# Trofodotiko.net
KiCad netlist of a schematic drawn in EAGLE
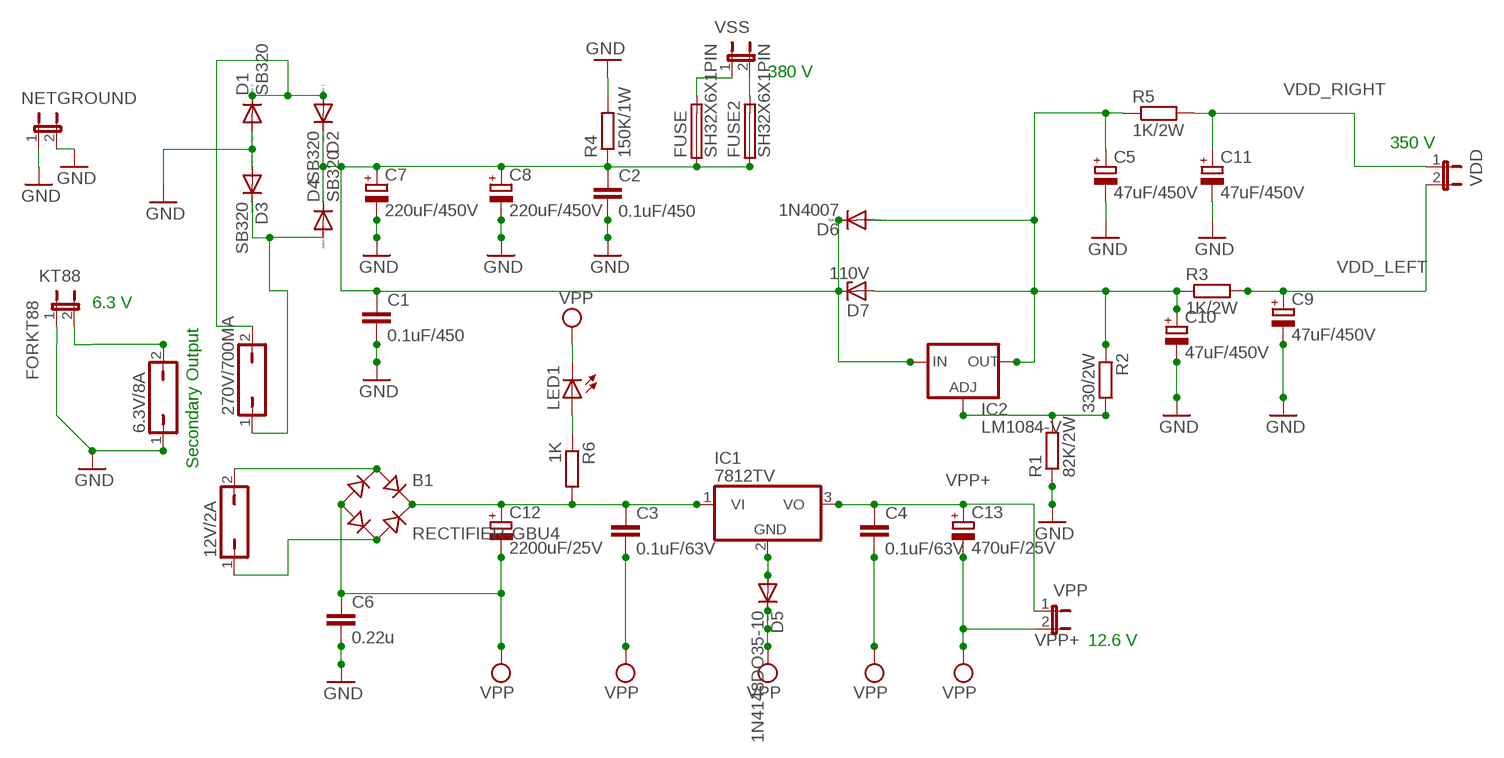
[diagram p0: schematic, sheet 1]

(export (version "E")
  (design (tool "Eeschema 10.0.6"))
  (components
    (comp (ref "6.3V/8A")
      (value "JP1Q")
      (footprint "eagle-import:JP1")
      (libsource (lib "eagle-import") (part "JP1Q"))
    )
    (comp (ref "12V/2A")
      (value "JP1Q")
      (footprint "eagle-import:JP1")
      (libsource (lib "eagle-import") (part "JP1Q"))
    )
    (comp (ref "270V/700MA")
      (value "JP1Q")
      (footprint "eagle-import:JP1")
      (libsource (lib "eagle-import") (part "JP1Q"))
    )
    (comp (ref "B1")
      (value "RECTIFIER-GBU4")
      (footprint "eagle-import:GBU4")
      (libsource (lib "eagle-import") (part "RECTIFIER-GBU4"))
    )
    (comp (ref "C1")
      (value "0.1uF/450")
      (footprint "eagle-import:C10B5")
      (libsource (lib "eagle-import") (part "C10/5"))
    )
    (comp (ref "C2")
      (value "0.1uF/450")
      (footprint "eagle-import:C10B5")
      (libsource (lib "eagle-import") (part "C10/5"))
    )
    (comp (ref "C3")
      (value "0.1uF/63V")
      (footprint "eagle-import:C5B2.5")
      (libsource (lib "eagle-import") (part "C5/2.5"))
    )
    (comp (ref "C4")
      (value "0.1uF/63V")
      (footprint "eagle-import:C5B2.5")
      (libsource (lib "eagle-import") (part "C5/2.5"))
    )
    (comp (ref "C5")
      (value "47uF/450V")
      (footprint "eagle-import:E5-13")
      (libsource (lib "eagle-import") (part "CPOL-EUE5-13"))
    )
    (comp (ref "C6")
      (value "0.22u")
      (footprint "eagle-import:C0805K")
      (libsource (lib "eagle-import") (part "C-EUC0805K"))
    )
    (comp (ref "C7")
      (value "220uF/450V")
      (footprint "eagle-import:EB25D")
      (libsource (lib "eagle-import") (part "CPOL-EUE10-25"))
    )
    (comp (ref "C8")
      (value "220uF/450V")
      (footprint "eagle-import:EB25D")
      (libsource (lib "eagle-import") (part "CPOL-EUE10-25"))
    )
    (comp (ref "C9")
      (value "47uF/450V")
      (footprint "eagle-import:E5-13")
      (libsource (lib "eagle-import") (part "CPOL-EUE5-13"))
    )
    (comp (ref "C10")
      (value "47uF/450V")
      (footprint "eagle-import:E5-13")
      (libsource (lib "eagle-import") (part "CPOL-EUE5-13"))
    )
    (comp (ref "C11")
      (value "47uF/450V")
      (footprint "eagle-import:E5-13")
      (libsource (lib "eagle-import") (part "CPOL-EUE5-13"))
    )
    (comp (ref "C12")
      (value "2200uF/25V")
      (footprint "eagle-import:E5-13")
      (libsource (lib "eagle-import") (part "CPOL-EUE5-13"))
    )
    (comp (ref "C13")
      (value "470uF/25V")
      (footprint "eagle-import:E3,5-8")
      (libsource (lib "eagle-import") (part "CPOL-EUE3.5-8"))
    )
    (comp (ref "D1")
      (value "SB320")
      (footprint "eagle-import:DO201-15")
      (libsource (lib "eagle-import") (part "SB320"))
    )
    (comp (ref "D2")
      (value "SB320")
      (footprint "eagle-import:DO201-15")
      (libsource (lib "eagle-import") (part "SB320"))
    )
    (comp (ref "D3")
      (value "SB320")
      (footprint "eagle-import:DO201-15")
      (libsource (lib "eagle-import") (part "SB320"))
    )
    (comp (ref "D4")
      (value "SB320")
      (footprint "eagle-import:DO201-15")
      (libsource (lib "eagle-import") (part "SB320"))
    )
    (comp (ref "D5")
      (value "1N4148DO35-10")
      (footprint "eagle-import:DO35-10")
      (libsource (lib "eagle-import") (part "1N4148DO35-10"))
    )
    (comp (ref "D6")
      (value "1N4007")
      (footprint "eagle-import:DO15-12")
      (libsource (lib "eagle-import") (part "1N5060GP"))
    )
    (comp (ref "D7")
      (value "110V")
      (footprint "eagle-import:C1702-15")
      (libsource (lib "eagle-import") (part "1N5333"))
    )
    (comp (ref "FUSE")
      (value "SH32X6X1PIN")
      (footprint "eagle-import:SH32")
      (libsource (lib "eagle-import") (part "SH32X6X1PIN"))
    )
    (comp (ref "FUSE2")
      (value "SH32X6X1PIN")
      (footprint "eagle-import:SH32")
      (libsource (lib "eagle-import") (part "SH32X6X1PIN"))
    )
    (comp (ref "IC1")
      (value "7812TV")
      (footprint "eagle-import:TO220V")
      (libsource (lib "eagle-import") (part "78TV12"))
    )
    (comp (ref "IC2")
      (value "LM1084-V")
      (footprint "eagle-import:317TS")
      (libsource (lib "eagle-import") (part "LM1084-V"))
    )
    (comp (ref "KT88")
      (value "JP1E")
      (footprint "eagle-import:JP1")
      (libsource (lib "eagle-import") (part "JP1E"))
    )
    (comp (ref "LED1")
      (value "LEDSML0805")
      (footprint "eagle-import:SML0805")
      (libsource (lib "eagle-import") (part "LEDSML0805"))
    )
    (comp (ref "NETGROUND")
      (value "JP1E")
      (footprint "eagle-import:JP1")
      (libsource (lib "eagle-import") (part "JP1E"))
    )
    (comp (ref "R1")
      (value "82K/2W")
      (footprint "eagle-import:P0817_22")
      (libsource (lib "eagle-import") (part "R-EU_0817/22"))
    )
    (comp (ref "R2")
      (value "330/2W")
      (footprint "eagle-import:0411_12")
      (libsource (lib "eagle-import") (part "resistor_348_R-EU_0411/12"))
    )
    (comp (ref "R3")
      (value "1K/2W")
      (footprint "eagle-import:0411_12")
      (libsource (lib "eagle-import") (part "resistor_348_R-EU_0411/12"))
    )
    (comp (ref "R4")
      (value "150K/1W")
      (footprint "eagle-import:0411_15")
      (libsource (lib "eagle-import") (part "resistor_348_R-EU_0411/15"))
    )
    (comp (ref "R5")
      (value "1K/2W")
      (footprint "eagle-import:0411_12")
      (libsource (lib "eagle-import") (part "resistor_348_R-EU_0411/12"))
    )
    (comp (ref "R6")
      (value "1K")
      (footprint "eagle-import:R0805")
      (libsource (lib "eagle-import") (part "R-EU_R0805"))
    )
    (comp (ref "VDD")
      (value "JP1E")
      (footprint "eagle-import:JP1")
      (libsource (lib "eagle-import") (part "JP1E"))
    )
    (comp (ref "VPP")
      (value "JP1E")
      (footprint "eagle-import:JP1")
      (libsource (lib "eagle-import") (part "JP1E"))
    )
    (comp (ref "VSS")
      (value "JP1E")
      (footprint "eagle-import:JP1")
      (libsource (lib "eagle-import") (part "JP1E"))
    )
  )
  (nets
    (net (code "1") (name "/FORKT88") (class "Default")
      (node (ref "6.3V/8A") (pin "2") (pinfunction "2_2") (pintype "passive"))
      (node (ref "KT88") (pin "2") (pinfunction "2_2") (pintype "passive"))
    )
    (net (code "2") (name "/VDD_LEFT") (class "Default")
      (node (ref "C9") (pin "+") (pinfunction "+_+") (pintype "passive"))
      (node (ref "R3") (pin "2") (pinfunction "2_2") (pintype "passive"))
      (node (ref "VDD") (pin "2") (pinfunction "2_2") (pintype "passive"))
    )
    (net (code "3") (name "/VDD_RIGHT") (class "Default")
      (node (ref "C11") (pin "+") (pinfunction "+_+") (pintype "passive"))
      (node (ref "R5") (pin "2") (pinfunction "2_2") (pintype "passive"))
      (node (ref "VDD") (pin "1") (pinfunction "1_1") (pintype "passive"))
    )
    (net (code "4") (name "/VPP+") (class "Default")
      (node (ref "C13") (pin "+") (pinfunction "+_+") (pintype "passive"))
      (node (ref "C4") (pin "1") (pinfunction "1_1") (pintype "passive"))
      (node (ref "IC1") (pin "3") (pinfunction "VO_3") (pintype "passive"))
      (node (ref "VPP") (pin "1") (pinfunction "1_1") (pintype "passive"))
    )
    (net (code "5") (name "GND") (class "Default")
      (node (ref "6.3V/8A") (pin "1") (pinfunction "1_1") (pintype "passive"))
      (node (ref "C1") (pin "2") (pinfunction "2_2") (pintype "passive"))
      (node (ref "C10") (pin "-") (pinfunction "-_-") (pintype "passive"))
      (node (ref "C11") (pin "-") (pinfunction "-_-") (pintype "passive"))
      (node (ref "C2") (pin "2") (pinfunction "2_2") (pintype "passive"))
      (node (ref "C5") (pin "-") (pinfunction "-_-") (pintype "passive"))
      (node (ref "C6") (pin "2") (pinfunction "2_2") (pintype "passive"))
      (node (ref "C7") (pin "-") (pinfunction "-_-") (pintype "passive"))
      (node (ref "C8") (pin "-") (pinfunction "-_-") (pintype "passive"))
      (node (ref "C9") (pin "-") (pinfunction "-_-") (pintype "passive"))
      (node (ref "D1") (pin "A") (pinfunction "A_A") (pintype "passive"))
      (node (ref "D3") (pin "A") (pinfunction "A_A") (pintype "passive"))
      (node (ref "KT88") (pin "1") (pinfunction "1_1") (pintype "passive"))
      (node (ref "NETGROUND") (pin "1") (pinfunction "1_1") (pintype "passive"))
      (node (ref "NETGROUND") (pin "2") (pinfunction "2_2") (pintype "passive"))
      (node (ref "R1") (pin "1") (pinfunction "1_1") (pintype "passive"))
      (node (ref "R4") (pin "2") (pinfunction "2_2") (pintype "passive"))
    )
    (net (code "6") (name "Net-(12V/2A-Pad1)") (class "Default")
      (node (ref "12V/2A") (pin "1") (pinfunction "1_1") (pintype "passive"))
      (node (ref "B1") (pin "AC2") (pinfunction "AC2_AC2") (pintype "passive"))
    )
    (net (code "7") (name "Net-(12V/2A-Pad2)") (class "Default")
      (node (ref "12V/2A") (pin "2") (pinfunction "2_2") (pintype "passive"))
      (node (ref "B1") (pin "AC1") (pinfunction "AC1_AC1") (pintype "passive"))
    )
    (net (code "8") (name "Net-(270V/700MA-Pad1)") (class "Default")
      (node (ref "270V/700MA") (pin "1") (pinfunction "1_1") (pintype "passive"))
      (node (ref "D3") (pin "C") (pinfunction "C_C") (pintype "passive"))
      (node (ref "D4") (pin "A") (pinfunction "A_A") (pintype "passive"))
    )
    (net (code "9") (name "Net-(270V/700MA-Pad2)") (class "Default")
      (node (ref "270V/700MA") (pin "2") (pinfunction "2_2") (pintype "passive"))
      (node (ref "D1") (pin "C") (pinfunction "C_C") (pintype "passive"))
      (node (ref "D2") (pin "A") (pinfunction "A_A") (pintype "passive"))
    )
    (net (code "10") (name "Net-(FUSE-1)") (class "Default")
      (node (ref "C1") (pin "1") (pinfunction "1_1") (pintype "passive"))
      (node (ref "C2") (pin "1") (pinfunction "1_1") (pintype "passive"))
      (node (ref "C7") (pin "+") (pinfunction "+_+") (pintype "passive"))
      (node (ref "C8") (pin "+") (pinfunction "+_+") (pintype "passive"))
      (node (ref "D2") (pin "C") (pinfunction "C_C") (pintype "passive"))
      (node (ref "D4") (pin "C") (pinfunction "C_C") (pintype "passive"))
      (node (ref "D6") (pin "C") (pinfunction "C_C") (pintype "passive"))
      (node (ref "D7") (pin "C") (pinfunction "C_C") (pintype "passive"))
      (node (ref "FUSE") (pin "1A") (pinfunction "1_1A") (pintype "passive"))
      (node (ref "FUSE2") (pin "1A") (pinfunction "1_1A") (pintype "passive"))
      (node (ref "IC2") (pin "3") (pinfunction "IN_3") (pintype "input"))
      (node (ref "R4") (pin "1") (pinfunction "1_1") (pintype "passive"))
    )
    (net (code "11") (name "Net-(FUSE-2)") (class "Default")
      (node (ref "FUSE") (pin "2B") (pinfunction "2_2B") (pintype "passive"))
      (node (ref "VSS") (pin "1") (pinfunction "1_1") (pintype "passive"))
    )
    (net (code "12") (name "Net-(FUSE2-2)") (class "Default")
      (node (ref "FUSE2") (pin "2B") (pinfunction "2_2B") (pintype "passive"))
      (node (ref "VSS") (pin "2") (pinfunction "2_2") (pintype "passive"))
    )
    (net (code "13") (name "Net-(IC1-GND)") (class "Default")
      (node (ref "D5") (pin "A") (pinfunction "A_A") (pintype "passive"))
      (node (ref "IC1") (pin "2") (pinfunction "GND_2") (pintype "passive"))
    )
    (net (code "14") (name "Net-(IC1-VI)") (class "Default")
      (node (ref "B1") (pin "+") (pinfunction "+_+") (pintype "passive"))
      (node (ref "C12") (pin "+") (pinfunction "+_+") (pintype "passive"))
      (node (ref "C3") (pin "1") (pinfunction "1_1") (pintype "passive"))
      (node (ref "IC1") (pin "1") (pinfunction "VI_1") (pintype "input"))
      (node (ref "R6") (pin "2") (pinfunction "2_2") (pintype "passive"))
    )
    (net (code "15") (name "Net-(IC2-ADJ)") (class "Default")
      (node (ref "IC2") (pin "1") (pinfunction "ADJ_1") (pintype "input"))
      (node (ref "R1") (pin "2") (pinfunction "2_2") (pintype "passive"))
      (node (ref "R2") (pin "2") (pinfunction "2_2") (pintype "passive"))
    )
    (net (code "16") (name "Net-(IC2-OUT)") (class "Default")
      (node (ref "C10") (pin "+") (pinfunction "+_+") (pintype "passive"))
      (node (ref "C5") (pin "+") (pinfunction "+_+") (pintype "passive"))
      (node (ref "D6") (pin "A") (pinfunction "A_A") (pintype "passive"))
      (node (ref "D7") (pin "A") (pinfunction "A_A") (pintype "passive"))
      (node (ref "IC2") (pin "2") (pinfunction "OUT_2") (pintype "passive"))
      (node (ref "R2") (pin "1") (pinfunction "1_1") (pintype "passive"))
      (node (ref "R3") (pin "1") (pinfunction "1_1") (pintype "passive"))
      (node (ref "R5") (pin "1") (pinfunction "1_1") (pintype "passive"))
    )
    (net (code "17") (name "Net-(LED1-PadA)") (class "Default")
      (node (ref "LED1") (pin "A") (pinfunction "A_A") (pintype "passive"))
      (node (ref "R6") (pin "1") (pinfunction "1_1") (pintype "passive"))
    )
    (net (code "18") (name "VPP") (class "Default")
      (node (ref "B1") (pin "-") (pinfunction "-_-") (pintype "passive"))
      (node (ref "C12") (pin "-") (pinfunction "-_-") (pintype "passive"))
      (node (ref "C13") (pin "-") (pinfunction "-_-") (pintype "passive"))
      (node (ref "C3") (pin "2") (pinfunction "2_2") (pintype "passive"))
      (node (ref "C4") (pin "2") (pinfunction "2_2") (pintype "passive"))
      (node (ref "C6") (pin "1") (pinfunction "1_1") (pintype "passive"))
      (node (ref "D5") (pin "C") (pinfunction "C_C") (pintype "passive"))
      (node (ref "LED1") (pin "C") (pinfunction "C_C") (pintype "passive"))
      (node (ref "VPP") (pin "2") (pinfunction "2_2") (pintype "passive"))
    )
  )
)
